# hcgs-midi-mud-led.net
KiCad netlist of a schematic drawn in EAGLE
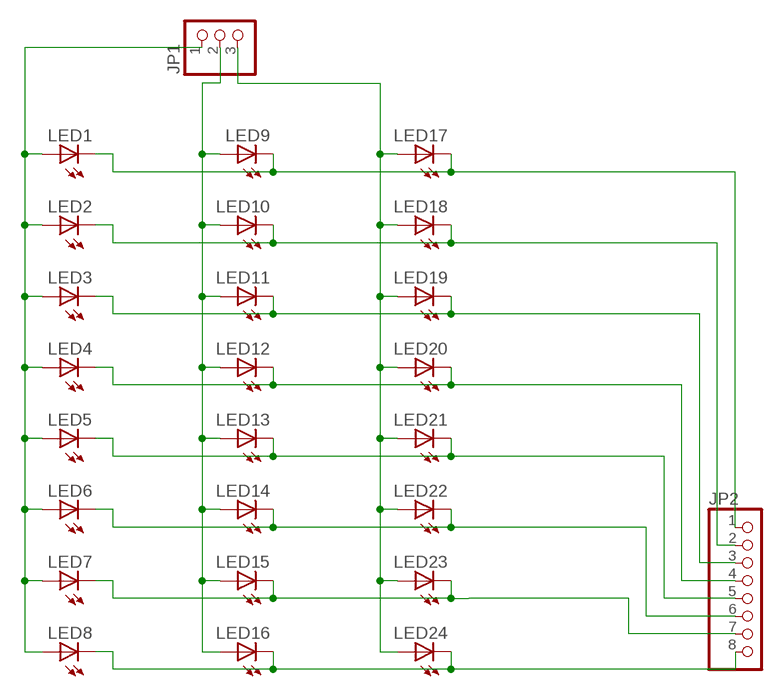
[diagram p0: schematic, sheet 1]

(export (version "E")
  (design (tool "Eeschema 10.0.6"))
  (components
    (comp (ref "JP1")
      (value "PINHD-1X3")
      (footprint "eagle-import:1X03")
      (libsource (lib "eagle-import") (part "PINHD-1X3"))
    )
    (comp (ref "JP2")
      (value "PINHD-1X8")
      (footprint "eagle-import:1X08")
      (libsource (lib "eagle-import") (part "PINHD-1X8"))
    )
    (comp (ref "LED1")
      (value "LED5MM")
      (footprint "eagle-import:LED5MM")
      (libsource (lib "eagle-import") (part "LED5MM"))
    )
    (comp (ref "LED2")
      (value "LED5MM")
      (footprint "eagle-import:LED5MM")
      (libsource (lib "eagle-import") (part "LED5MM"))
    )
    (comp (ref "LED3")
      (value "LED5MM")
      (footprint "eagle-import:LED5MM")
      (libsource (lib "eagle-import") (part "LED5MM"))
    )
    (comp (ref "LED4")
      (value "LED5MM")
      (footprint "eagle-import:LED5MM")
      (libsource (lib "eagle-import") (part "LED5MM"))
    )
    (comp (ref "LED5")
      (value "LED5MM")
      (footprint "eagle-import:LED5MM")
      (libsource (lib "eagle-import") (part "LED5MM"))
    )
    (comp (ref "LED6")
      (value "LED5MM")
      (footprint "eagle-import:LED5MM")
      (libsource (lib "eagle-import") (part "LED5MM"))
    )
    (comp (ref "LED7")
      (value "LED5MM")
      (footprint "eagle-import:LED5MM")
      (libsource (lib "eagle-import") (part "LED5MM"))
    )
    (comp (ref "LED8")
      (value "LED5MM")
      (footprint "eagle-import:LED5MM")
      (libsource (lib "eagle-import") (part "LED5MM"))
    )
    (comp (ref "LED9")
      (value "LED5MM")
      (footprint "eagle-import:LED5MM")
      (libsource (lib "eagle-import") (part "LED5MM"))
    )
    (comp (ref "LED10")
      (value "LED5MM")
      (footprint "eagle-import:LED5MM")
      (libsource (lib "eagle-import") (part "LED5MM"))
    )
    (comp (ref "LED11")
      (value "LED5MM")
      (footprint "eagle-import:LED5MM")
      (libsource (lib "eagle-import") (part "LED5MM"))
    )
    (comp (ref "LED12")
      (value "LED5MM")
      (footprint "eagle-import:LED5MM")
      (libsource (lib "eagle-import") (part "LED5MM"))
    )
    (comp (ref "LED13")
      (value "LED5MM")
      (footprint "eagle-import:LED5MM")
      (libsource (lib "eagle-import") (part "LED5MM"))
    )
    (comp (ref "LED14")
      (value "LED5MM")
      (footprint "eagle-import:LED5MM")
      (libsource (lib "eagle-import") (part "LED5MM"))
    )
    (comp (ref "LED15")
      (value "LED5MM")
      (footprint "eagle-import:LED5MM")
      (libsource (lib "eagle-import") (part "LED5MM"))
    )
    (comp (ref "LED16")
      (value "LED5MM")
      (footprint "eagle-import:LED5MM")
      (libsource (lib "eagle-import") (part "LED5MM"))
    )
    (comp (ref "LED17")
      (value "LED5MM")
      (footprint "eagle-import:LED5MM")
      (libsource (lib "eagle-import") (part "LED5MM"))
    )
    (comp (ref "LED18")
      (value "LED5MM")
      (footprint "eagle-import:LED5MM")
      (libsource (lib "eagle-import") (part "LED5MM"))
    )
    (comp (ref "LED19")
      (value "LED5MM")
      (footprint "eagle-import:LED5MM")
      (libsource (lib "eagle-import") (part "LED5MM"))
    )
    (comp (ref "LED20")
      (value "LED5MM")
      (footprint "eagle-import:LED5MM")
      (libsource (lib "eagle-import") (part "LED5MM"))
    )
    (comp (ref "LED21")
      (value "LED5MM")
      (footprint "eagle-import:LED5MM")
      (libsource (lib "eagle-import") (part "LED5MM"))
    )
    (comp (ref "LED22")
      (value "LED5MM")
      (footprint "eagle-import:LED5MM")
      (libsource (lib "eagle-import") (part "LED5MM"))
    )
    (comp (ref "LED23")
      (value "LED5MM")
      (footprint "eagle-import:LED5MM")
      (libsource (lib "eagle-import") (part "LED5MM"))
    )
    (comp (ref "LED24")
      (value "LED5MM")
      (footprint "eagle-import:LED5MM")
      (libsource (lib "eagle-import") (part "LED5MM"))
    )
  )
  (nets
    (net (code "1") (name "Net-(JP1-Pad1)") (class "Default")
      (node (ref "JP1") (pin "1") (pinfunction "1_1") (pintype "passive"))
      (node (ref "LED1") (pin "A") (pinfunction "A_A") (pintype "passive"))
      (node (ref "LED2") (pin "A") (pinfunction "A_A") (pintype "passive"))
      (node (ref "LED3") (pin "A") (pinfunction "A_A") (pintype "passive"))
      (node (ref "LED4") (pin "A") (pinfunction "A_A") (pintype "passive"))
      (node (ref "LED5") (pin "A") (pinfunction "A_A") (pintype "passive"))
      (node (ref "LED6") (pin "A") (pinfunction "A_A") (pintype "passive"))
      (node (ref "LED7") (pin "A") (pinfunction "A_A") (pintype "passive"))
      (node (ref "LED8") (pin "A") (pinfunction "A_A") (pintype "passive"))
    )
    (net (code "2") (name "Net-(JP1-Pad2)") (class "Default")
      (node (ref "JP1") (pin "2") (pinfunction "2_2") (pintype "passive"))
      (node (ref "LED10") (pin "A") (pinfunction "A_A") (pintype "passive"))
      (node (ref "LED11") (pin "A") (pinfunction "A_A") (pintype "passive"))
      (node (ref "LED12") (pin "A") (pinfunction "A_A") (pintype "passive"))
      (node (ref "LED13") (pin "A") (pinfunction "A_A") (pintype "passive"))
      (node (ref "LED14") (pin "A") (pinfunction "A_A") (pintype "passive"))
      (node (ref "LED15") (pin "A") (pinfunction "A_A") (pintype "passive"))
      (node (ref "LED16") (pin "A") (pinfunction "A_A") (pintype "passive"))
      (node (ref "LED9") (pin "A") (pinfunction "A_A") (pintype "passive"))
    )
    (net (code "3") (name "Net-(JP1-Pad3)") (class "Default")
      (node (ref "JP1") (pin "3") (pinfunction "3_3") (pintype "passive"))
      (node (ref "LED17") (pin "A") (pinfunction "A_A") (pintype "passive"))
      (node (ref "LED18") (pin "A") (pinfunction "A_A") (pintype "passive"))
      (node (ref "LED19") (pin "A") (pinfunction "A_A") (pintype "passive"))
      (node (ref "LED20") (pin "A") (pinfunction "A_A") (pintype "passive"))
      (node (ref "LED21") (pin "A") (pinfunction "A_A") (pintype "passive"))
      (node (ref "LED22") (pin "A") (pinfunction "A_A") (pintype "passive"))
      (node (ref "LED23") (pin "A") (pinfunction "A_A") (pintype "passive"))
      (node (ref "LED24") (pin "A") (pinfunction "A_A") (pintype "passive"))
    )
    (net (code "4") (name "Net-(LED1-C)") (class "Default")
      (node (ref "JP2") (pin "1") (pinfunction "1_1") (pintype "passive"))
      (node (ref "LED1") (pin "K") (pinfunction "C_K") (pintype "passive"))
      (node (ref "LED17") (pin "K") (pinfunction "C_K") (pintype "passive"))
      (node (ref "LED9") (pin "K") (pinfunction "C_K") (pintype "passive"))
    )
    (net (code "5") (name "Net-(LED10-C)") (class "Default")
      (node (ref "JP2") (pin "2") (pinfunction "2_2") (pintype "passive"))
      (node (ref "LED10") (pin "K") (pinfunction "C_K") (pintype "passive"))
      (node (ref "LED18") (pin "K") (pinfunction "C_K") (pintype "passive"))
      (node (ref "LED2") (pin "K") (pinfunction "C_K") (pintype "passive"))
    )
    (net (code "6") (name "Net-(LED11-C)") (class "Default")
      (node (ref "JP2") (pin "3") (pinfunction "3_3") (pintype "passive"))
      (node (ref "LED11") (pin "K") (pinfunction "C_K") (pintype "passive"))
      (node (ref "LED19") (pin "K") (pinfunction "C_K") (pintype "passive"))
      (node (ref "LED3") (pin "K") (pinfunction "C_K") (pintype "passive"))
    )
    (net (code "7") (name "Net-(LED12-C)") (class "Default")
      (node (ref "JP2") (pin "4") (pinfunction "4_4") (pintype "passive"))
      (node (ref "LED12") (pin "K") (pinfunction "C_K") (pintype "passive"))
      (node (ref "LED20") (pin "K") (pinfunction "C_K") (pintype "passive"))
      (node (ref "LED4") (pin "K") (pinfunction "C_K") (pintype "passive"))
    )
    (net (code "8") (name "Net-(LED13-C)") (class "Default")
      (node (ref "JP2") (pin "5") (pinfunction "5_5") (pintype "passive"))
      (node (ref "LED13") (pin "K") (pinfunction "C_K") (pintype "passive"))
      (node (ref "LED21") (pin "K") (pinfunction "C_K") (pintype "passive"))
      (node (ref "LED5") (pin "K") (pinfunction "C_K") (pintype "passive"))
    )
    (net (code "9") (name "Net-(LED14-C)") (class "Default")
      (node (ref "JP2") (pin "6") (pinfunction "6_6") (pintype "passive"))
      (node (ref "LED14") (pin "K") (pinfunction "C_K") (pintype "passive"))
      (node (ref "LED22") (pin "K") (pinfunction "C_K") (pintype "passive"))
      (node (ref "LED6") (pin "K") (pinfunction "C_K") (pintype "passive"))
    )
    (net (code "10") (name "Net-(LED15-C)") (class "Default")
      (node (ref "JP2") (pin "7") (pinfunction "7_7") (pintype "passive"))
      (node (ref "LED15") (pin "K") (pinfunction "C_K") (pintype "passive"))
      (node (ref "LED23") (pin "K") (pinfunction "C_K") (pintype "passive"))
      (node (ref "LED7") (pin "K") (pinfunction "C_K") (pintype "passive"))
    )
    (net (code "11") (name "Net-(LED16-C)") (class "Default")
      (node (ref "JP2") (pin "8") (pinfunction "8_8") (pintype "passive"))
      (node (ref "LED16") (pin "K") (pinfunction "C_K") (pintype "passive"))
      (node (ref "LED24") (pin "K") (pinfunction "C_K") (pintype "passive"))
      (node (ref "LED8") (pin "K") (pinfunction "C_K") (pintype "passive"))
    )
  )
)
